# Sheet1.net
KiCad netlist of a schematic drawn in Altium Designer
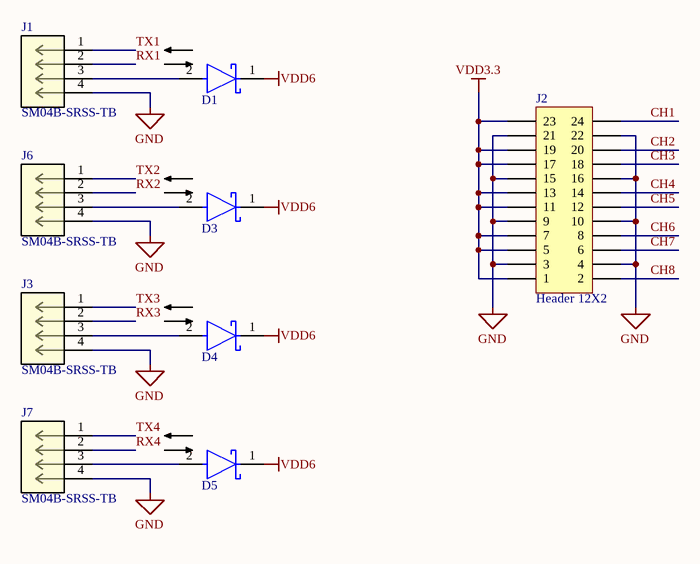
[diagram p0: Sheet1.SchDoc]

(export (version "E")
  (design (tool "Eeschema 10.0.6"))
  (components
    (comp (ref "D1")
      (value "VS-10MQ100NTRPBF")
      (footprint "FP-95400-MFG")
      (description "DIODE SCHOTTKY 100V 1A SMA")
      (fields
        (field (name "OCTOPART") "https://octopart.com/vs-10mq100ntrpbf-vishay-44340924")
        (field (name "MANUFACTURER") "Vishay")
      )
      (libsource (lib "Altium Content Vault") (part "c1678fac7984e62e0809fbf79c06691"))
    )
    (comp (ref "D3")
      (value "VS-10MQ100NTRPBF")
      (footprint "FP-95400-MFG")
      (description "DIODE SCHOTTKY 100V 1A SMA")
      (fields
        (field (name "OCTOPART") "https://octopart.com/vs-10mq100ntrpbf-vishay-44340924")
        (field (name "MANUFACTURER") "Vishay")
      )
      (libsource (lib "Altium Content Vault") (part "c1678fac7984e62e0809fbf79c06691"))
    )
    (comp (ref "D4")
      (value "VS-10MQ100NTRPBF")
      (footprint "FP-95400-MFG")
      (description "DIODE SCHOTTKY 100V 1A SMA")
      (fields
        (field (name "OCTOPART") "https://octopart.com/vs-10mq100ntrpbf-vishay-44340924")
        (field (name "MANUFACTURER") "Vishay")
      )
      (libsource (lib "Altium Content Vault") (part "c1678fac7984e62e0809fbf79c06691"))
    )
    (comp (ref "D5")
      (value "VS-10MQ100NTRPBF")
      (footprint "FP-95400-MFG")
      (description "DIODE SCHOTTKY 100V 1A SMA")
      (fields
        (field (name "OCTOPART") "https://octopart.com/vs-10mq100ntrpbf-vishay-44340924")
        (field (name "MANUFACTURER") "Vishay")
      )
      (libsource (lib "Altium Content Vault") (part "c1678fac7984e62e0809fbf79c06691"))
    )
    (comp (ref "J1")
      (value "SM04B-SRSS-TB")
      (footprint "CONN_SM04B-SRSS-TB_JST")
      (description "No Description Available")
      (libsource (lib "SM04B-SRSS-TB") (part "SM04B-SRSS-TB"))
    )
    (comp (ref "J2")
      (value "Header 12X2")
      (footprint "jst_pad24")
      (description "Header, 12-Pin, Dual row")
      (fields (field (name "PUBLISHER") "Altium Limited"))
      (libsource (lib "Miscellaneous Connectors") (part "Header 12X2"))
    )
    (comp (ref "J3")
      (value "SM04B-SRSS-TB")
      (footprint "CONN_SM04B-SRSS-TB_JST")
      (description "No Description Available")
      (libsource (lib "SM04B-SRSS-TB") (part "SM04B-SRSS-TB"))
    )
    (comp (ref "J6")
      (value "SM04B-SRSS-TB")
      (footprint "CONN_SM04B-SRSS-TB_JST")
      (description "No Description Available")
      (libsource (lib "SM04B-SRSS-TB") (part "SM04B-SRSS-TB"))
    )
    (comp (ref "J7")
      (value "SM04B-SRSS-TB")
      (footprint "CONN_SM04B-SRSS-TB_JST")
      (description "No Description Available")
      (libsource (lib "SM04B-SRSS-TB") (part "SM04B-SRSS-TB"))
    )
  )
  (nets
    (net (code "1") (name "/CH1") (class "Default")
      (node (ref "J2") (pin "24") (pinfunction "24_24") (pintype "passive"))
    )
    (net (code "2") (name "/CH2") (class "Default")
      (node (ref "J2") (pin "20") (pinfunction "20_20") (pintype "passive"))
    )
    (net (code "3") (name "/CH3") (class "Default")
      (node (ref "J2") (pin "18") (pinfunction "18_18") (pintype "passive"))
    )
    (net (code "4") (name "/CH4") (class "Default")
      (node (ref "J2") (pin "14") (pinfunction "14_14") (pintype "passive"))
    )
    (net (code "5") (name "/CH5") (class "Default")
      (node (ref "J2") (pin "12") (pinfunction "12_12") (pintype "passive"))
    )
    (net (code "6") (name "/CH6") (class "Default")
      (node (ref "J2") (pin "8") (pinfunction "8_8") (pintype "passive"))
    )
    (net (code "7") (name "/CH7") (class "Default")
      (node (ref "J2") (pin "6") (pinfunction "6_6") (pintype "passive"))
    )
    (net (code "8") (name "/CH8") (class "Default")
      (node (ref "J2") (pin "2") (pinfunction "2_2") (pintype "passive"))
    )
    (net (code "9") (name "/RX1") (class "Default")
      (node (ref "J1") (pin "2") (pinfunction "2_2") (pintype "passive"))
    )
    (net (code "10") (name "/RX2") (class "Default")
      (node (ref "J6") (pin "2") (pinfunction "2_2") (pintype "passive"))
    )
    (net (code "11") (name "/RX3") (class "Default")
      (node (ref "J3") (pin "2") (pinfunction "2_2") (pintype "passive"))
    )
    (net (code "12") (name "/RX4") (class "Default")
      (node (ref "J7") (pin "2") (pinfunction "2_2") (pintype "passive"))
    )
    (net (code "13") (name "/TX1") (class "Default")
      (node (ref "J1") (pin "1") (pinfunction "1_1") (pintype "passive"))
    )
    (net (code "14") (name "/TX2") (class "Default")
      (node (ref "J6") (pin "1") (pinfunction "1_1") (pintype "passive"))
    )
    (net (code "15") (name "/TX3") (class "Default")
      (node (ref "J3") (pin "1") (pinfunction "1_1") (pintype "passive"))
    )
    (net (code "16") (name "/TX4") (class "Default")
      (node (ref "J7") (pin "1") (pinfunction "1_1") (pintype "passive"))
    )
    (net (code "17") (name "GND") (class "Default")
      (node (ref "J1") (pin "4") (pinfunction "4_4") (pintype "passive"))
      (node (ref "J2") (pin "10") (pinfunction "10_10") (pintype "passive"))
      (node (ref "J2") (pin "15") (pinfunction "15_15") (pintype "passive"))
      (node (ref "J2") (pin "16") (pinfunction "16_16") (pintype "passive"))
      (node (ref "J2") (pin "21") (pinfunction "21_21") (pintype "passive"))
      (node (ref "J2") (pin "22") (pinfunction "22_22") (pintype "passive"))
      (node (ref "J2") (pin "3") (pinfunction "3_3") (pintype "passive"))
      (node (ref "J2") (pin "4") (pinfunction "4_4") (pintype "passive"))
      (node (ref "J2") (pin "9") (pinfunction "9_9") (pintype "passive"))
      (node (ref "J3") (pin "4") (pinfunction "4_4") (pintype "passive"))
      (node (ref "J6") (pin "4") (pinfunction "4_4") (pintype "passive"))
      (node (ref "J7") (pin "4") (pinfunction "4_4") (pintype "passive"))
    )
    (net (code "18") (name "Net-(D1-A)") (class "Default")
      (node (ref "D1") (pin "2") (pinfunction "A_2") (pintype "passive"))
      (node (ref "J1") (pin "3") (pinfunction "3_3") (pintype "passive"))
    )
    (net (code "19") (name "Net-(D3-A)") (class "Default")
      (node (ref "D3") (pin "2") (pinfunction "A_2") (pintype "passive"))
      (node (ref "J6") (pin "3") (pinfunction "3_3") (pintype "passive"))
    )
    (net (code "20") (name "Net-(D4-A)") (class "Default")
      (node (ref "D4") (pin "2") (pinfunction "A_2") (pintype "passive"))
      (node (ref "J3") (pin "3") (pinfunction "3_3") (pintype "passive"))
    )
    (net (code "21") (name "Net-(D5-A)") (class "Default")
      (node (ref "D5") (pin "2") (pinfunction "A_2") (pintype "passive"))
      (node (ref "J7") (pin "3") (pinfunction "3_3") (pintype "passive"))
    )
    (net (code "22") (name "VDD3.3") (class "Default")
      (node (ref "J2") (pin "1") (pinfunction "1_1") (pintype "passive"))
      (node (ref "J2") (pin "11") (pinfunction "11_11") (pintype "passive"))
      (node (ref "J2") (pin "13") (pinfunction "13_13") (pintype "passive"))
      (node (ref "J2") (pin "17") (pinfunction "17_17") (pintype "passive"))
      (node (ref "J2") (pin "19") (pinfunction "19_19") (pintype "passive"))
      (node (ref "J2") (pin "23") (pinfunction "23_23") (pintype "passive"))
      (node (ref "J2") (pin "5") (pinfunction "5_5") (pintype "passive"))
      (node (ref "J2") (pin "7") (pinfunction "7_7") (pintype "passive"))
    )
    (net (code "23") (name "VDD6") (class "Default")
      (node (ref "D1") (pin "1") (pinfunction "C_1") (pintype "passive"))
      (node (ref "D3") (pin "1") (pinfunction "C_1") (pintype "passive"))
      (node (ref "D4") (pin "1") (pinfunction "C_1") (pintype "passive"))
      (node (ref "D5") (pin "1") (pinfunction "C_1") (pintype "passive"))
    )
  )
)
